# main_board.net
KiCad netlist of a schematic drawn in EAGLE
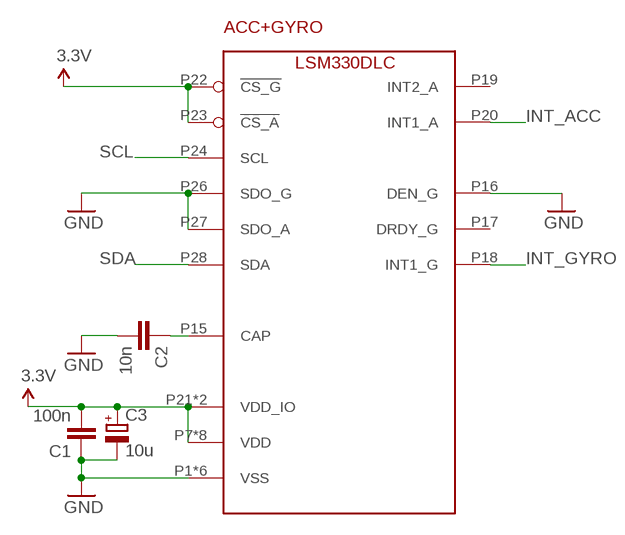
[diagram p0: schematic, sheet 1]

(export (version "E")
  (design (tool "Eeschema 10.0.6"))
  (components
    (comp (ref "ACC+GYRO")
      (value "LSM330DLC")
      (footprint "eagle-import:LGA_4X5X1P1_28L")
      (libsource (lib "eagle-import") (part "LSM330DLC"))
    )
    (comp (ref "C1")
      (value "100n")
      (footprint "eagle-import:C0805")
      (libsource (lib "eagle-import") (part "C-EUC0805"))
    )
    (comp (ref "C2")
      (value "10n")
      (footprint "eagle-import:C0805")
      (libsource (lib "eagle-import") (part "C-EUC0805"))
    )
    (comp (ref "C3")
      (value "10u")
      (footprint "eagle-import:SMC_A")
      (libsource (lib "eagle-import") (part "CPOL-EUSMCA"))
    )
  )
  (nets
    (net (code "1") (name "/INT_ACC") (class "Default")
      (node (ref "ACC+GYRO") (pin "P20") (pinfunction "INT1_A_P20") (pintype "output"))
    )
    (net (code "2") (name "/INT_GYRO") (class "Default")
      (node (ref "ACC+GYRO") (pin "P18") (pinfunction "INT1_G_P18") (pintype "output"))
    )
    (net (code "3") (name "/SCL") (class "Default")
      (node (ref "ACC+GYRO") (pin "P24") (pinfunction "SCL_P24") (pintype "input"))
    )
    (net (code "4") (name "/SDA") (class "Default")
      (node (ref "ACC+GYRO") (pin "P28") (pinfunction "SDA_P28") (pintype "input"))
    )
    (net (code "5") (name "3.3V") (class "Default")
      (node (ref "ACC+GYRO") (pin "P10") (pinfunction "VDD_P10") (pintype "power_in"))
      (node (ref "ACC+GYRO") (pin "P11") (pinfunction "VDD_P11") (pintype "power_in"))
      (node (ref "ACC+GYRO") (pin "P12") (pinfunction "VDD_P12") (pintype "power_in"))
      (node (ref "ACC+GYRO") (pin "P13") (pinfunction "VDD_P13") (pintype "power_in"))
      (node (ref "ACC+GYRO") (pin "P14") (pinfunction "VDD_P14") (pintype "power_in"))
      (node (ref "ACC+GYRO") (pin "P21") (pinfunction "VDD_IO_P21") (pintype "power_in"))
      (node (ref "ACC+GYRO") (pin "P22") (pinfunction "~{CS_G}_P22") (pintype "input"))
      (node (ref "ACC+GYRO") (pin "P23") (pinfunction "~{CS_A}_P23") (pintype "input"))
      (node (ref "ACC+GYRO") (pin "P25") (pinfunction "VDD_IO_P25") (pintype "power_in"))
      (node (ref "ACC+GYRO") (pin "P7") (pinfunction "VDD_P7") (pintype "power_in"))
      (node (ref "ACC+GYRO") (pin "P8") (pinfunction "VDD_P8") (pintype "power_in"))
      (node (ref "ACC+GYRO") (pin "P9") (pinfunction "VDD_P9") (pintype "power_in"))
      (node (ref "C1") (pin "2") (pinfunction "2_2") (pintype "passive"))
      (node (ref "C3") (pin "+") (pinfunction "+_+") (pintype "passive"))
    )
    (net (code "6") (name "GND") (class "Default")
      (node (ref "ACC+GYRO") (pin "P1") (pinfunction "VSS_P1") (pintype "power_in"))
      (node (ref "ACC+GYRO") (pin "P16") (pinfunction "DEN_G_P16") (pintype "input"))
      (node (ref "ACC+GYRO") (pin "P2") (pinfunction "VSS_P2") (pintype "power_in"))
      (node (ref "ACC+GYRO") (pin "P26") (pinfunction "SDO_G_P26") (pintype "output"))
      (node (ref "ACC+GYRO") (pin "P27") (pinfunction "SDO_A_P27") (pintype "output"))
      (node (ref "ACC+GYRO") (pin "P3") (pinfunction "VSS_P3") (pintype "power_in"))
      (node (ref "ACC+GYRO") (pin "P4") (pinfunction "VSS_P4") (pintype "power_in"))
      (node (ref "ACC+GYRO") (pin "P5") (pinfunction "VSS_P5") (pintype "power_in"))
      (node (ref "ACC+GYRO") (pin "P6") (pinfunction "VSS_P6") (pintype "power_in"))
      (node (ref "C1") (pin "1") (pinfunction "1_1") (pintype "passive"))
      (node (ref "C2") (pin "2") (pinfunction "2_2") (pintype "passive"))
      (node (ref "C3") (pin "-") (pinfunction "-_-") (pintype "passive"))
    )
    (net (code "7") (name "Net-(ACC+GYRO-CAP)") (class "Default")
      (node (ref "ACC+GYRO") (pin "P15") (pinfunction "CAP_P15") (pintype "power_in"))
      (node (ref "C2") (pin "1") (pinfunction "1_1") (pintype "passive"))
    )
    (net (code "8") (name "unconnected-(ACC+GYRO-DRDY_G-PadP17)") (class "Default")
      (node (ref "ACC+GYRO") (pin "P17") (pinfunction "DRDY_G_P17") (pintype "output"))
    )
    (net (code "9") (name "unconnected-(ACC+GYRO-INT2_A-PadP19)") (class "Default")
      (node (ref "ACC+GYRO") (pin "P19") (pinfunction "INT2_A_P19") (pintype "output"))
    )
  )
)
